# Power.net
KiCad netlist of a schematic drawn in Altium Designer
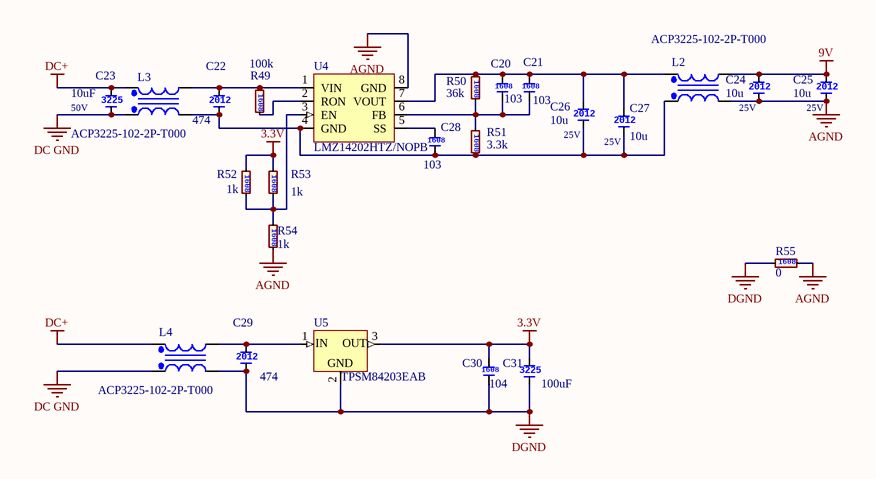
[diagram p0: Power.SchDoc]

(export (version "E")
  (design (tool "Eeschema 10.0.6"))
  (components
    (comp (ref "C20")
      (value "GCD188R71H103KA01D")
      (footprint "C1608")
      (description "セラコン1608サイズ")
      (fields (field (name "TAG") "103") (field (name "VOLTAGE") "50V"))
      (libsource (lib "Audio") (part "C1608"))
    )
    (comp (ref "C21")
      (value "GCD188R71H103KA01D")
      (footprint "C1608")
      (description "セラコン1608サイズ")
      (fields (field (name "TAG") "103") (field (name "VOLTAGE") "50V"))
      (libsource (lib "Audio") (part "C1608"))
    )
    (comp (ref "C22")
      (value "GRM21BR71H474MA88")
      (footprint "C2012")
      (description "セラコン2012サイズ")
      (fields (field (name "TAG") "474") (field (name "VOLTAGE") "50V"))
      (libsource (lib "Audio") (part "C2012"))
    )
    (comp (ref "C23")
      (value "UMK325C7106MM-T")
      (footprint "C3225")
      (description "セラコン3225サイズ")
      (fields (field (name "TAG") "10uF") (field (name "VOLTAGE") "50V"))
      (libsource (lib "Audio") (part "C3225"))
    )
    (comp (ref "C24")
      (value "TMK212BBJ106MG-T")
      (footprint "C2012")
      (description "セラコン2012サイズ")
      (fields (field (name "TAG") "10u") (field (name "VOLTAGE") "25V"))
      (libsource (lib "Audio") (part "C2012"))
    )
    (comp (ref "C25")
      (value "TMK212BBJ106MG-T")
      (footprint "C2012")
      (description "セラコン2012サイズ")
      (fields (field (name "TAG") "10u") (field (name "VOLTAGE") "25V"))
      (libsource (lib "Audio") (part "C2012"))
    )
    (comp (ref "C26")
      (value "TMK212BBJ106MG-T")
      (footprint "C2012")
      (description "セラコン2012サイズ")
      (fields (field (name "TAG") "10u") (field (name "VOLTAGE") "25V"))
      (libsource (lib "Audio") (part "C2012"))
    )
    (comp (ref "C27")
      (value "TMK212BBJ106MG-T")
      (footprint "C2012")
      (description "セラコン2012サイズ")
      (fields (field (name "TAG") "10u") (field (name "VOLTAGE") "25V"))
      (libsource (lib "Audio") (part "C2012"))
    )
    (comp (ref "C28")
      (value "GCD188R71H103KA01D")
      (footprint "C1608")
      (description "セラコン1608サイズ")
      (fields (field (name "TAG") "103") (field (name "VOLTAGE") "50V"))
      (libsource (lib "Audio") (part "C1608"))
    )
    (comp (ref "C29")
      (value "GRM21BR71H474MA88")
      (footprint "C2012")
      (description "セラコン2012サイズ")
      (fields (field (name "TAG") "474") (field (name "VOLTAGE") "50V"))
      (libsource (lib "Audio") (part "C2012"))
    )
    (comp (ref "C30")
      (value "CGA3E2X7R1H104K080AA")
      (footprint "C1608")
      (description "セラコン1608サイズ")
      (fields (field (name "TAG") "104") (field (name "VOLTAGE") "50V"))
      (libsource (lib "Audio") (part "C1608"))
    )
    (comp (ref "C31")
      (value "EMK325ABJ107MM-T")
      (footprint "C3225")
      (description "セラコン3225サイズ")
      (fields (field (name "TAG") "100uF") (field (name "VOLTAGE") "50V"))
      (libsource (lib "Audio") (part "C3225"))
    )
    (comp (ref "L2")
      (value "ACP3225-102-2P-T000")
      (footprint "ACM3225")
      (description "コモンモード,1A,4ピン")
      (libsource (lib "Audio") (part "ACM3225"))
    )
    (comp (ref "L3")
      (value "ACP3225-102-2P-T000")
      (footprint "ACM3225")
      (description "コモンモード,1A,4ピン")
      (libsource (lib "Audio Prj") (part "ACM3225"))
    )
    (comp (ref "L4")
      (value "ACP3225-102-2P-T000")
      (footprint "ACM3225")
      (description "コモンモード,1A,4ピン")
      (libsource (lib "Audio") (part "ACM3225"))
    )
    (comp (ref "R49")
      (value "ERJ-PA3F1003V")
      (footprint "R1608")
      (description "厚膜チップ抵抗1608サイズ")
      (fields (field (name "TAG") "100k"))
      (libsource (lib "Schlib1") (part "TF1608"))
    )
    (comp (ref "R50")
      (value "ERJ-PA3F3602V")
      (footprint "R1608")
      (description "厚膜チップ抵抗1608サイズ")
      (fields (field (name "TAG") "36k"))
      (libsource (lib "Schlib1") (part "TF1608"))
    )
    (comp (ref "R51")
      (value "ERJ-PA3F3301V")
      (footprint "R1608")
      (description "厚膜チップ抵抗1608サイズ")
      (fields (field (name "TAG") "3.3k"))
      (libsource (lib "Schlib1") (part "TF1608"))
    )
    (comp (ref "R52")
      (value "ERJ-PA3F1000V")
      (footprint "R1608")
      (description "厚膜チップ抵抗1608サイズ")
      (fields (field (name "TAG") "1k"))
      (libsource (lib "Schlib1") (part "TF1608"))
    )
    (comp (ref "R53")
      (value "ERJ-PA3F1000V")
      (footprint "R1608")
      (description "厚膜チップ抵抗1608サイズ")
      (fields (field (name "TAG") "1k"))
      (libsource (lib "Schlib1") (part "TF1608"))
    )
    (comp (ref "R54")
      (value "ERJ-PA3F1000V")
      (footprint "R1608")
      (description "厚膜チップ抵抗1608サイズ")
      (fields (field (name "TAG") "1k"))
      (libsource (lib "Schlib1") (part "TF1608"))
    )
    (comp (ref "R55")
      (value "ERJ-S030R00V")
      (footprint "R1608")
      (description "厚膜チップ抵抗1608サイズ")
      (fields (field (name "TAG") "0"))
      (libsource (lib "") (part "TF1608_1"))
    )
    (comp (ref "U4")
      (value "LMZ14202HTZ/NOPB")
      (footprint "TO-PMOD-7")
      (description "DC DC CONVERTER 5-30V")
      (libsource (lib "Audio") (part "LMZ14202HTZ/NOPB"))
    )
    (comp (ref "U5")
      (value "TPSM84203EAB")
      (footprint "TO220-3")
      (description "DC DC CONVERTER 3.3V")
      (libsource (lib "Audio Prj") (part "TPSM84203EAB"))
    )
  )
  (nets
    (net (code "1") (name "3.3V") (class "Default")
      (node (ref "C30") (pin "2") (pinfunction "2_2") (pintype "passive"))
      (node (ref "C31") (pin "2") (pinfunction "2_2") (pintype "passive"))
      (node (ref "R52") (pin "1") (pinfunction "1_1") (pintype "passive"))
      (node (ref "R53") (pin "1") (pinfunction "1_1") (pintype "passive"))
      (node (ref "U5") (pin "3") (pinfunction "OUT_3") (pintype "output"))
    )
    (net (code "2") (name "9V") (class "Default")
      (node (ref "C24") (pin "2") (pinfunction "2_2") (pintype "passive"))
      (node (ref "C25") (pin "2") (pinfunction "2_2") (pintype "passive"))
      (node (ref "L2") (pin "4") (pinfunction "Pri+_4") (pintype "passive"))
    )
    (net (code "3") (name "AGND") (class "Default")
      (node (ref "C24") (pin "1") (pinfunction "1_1") (pintype "passive"))
      (node (ref "C25") (pin "1") (pinfunction "1_1") (pintype "passive"))
      (node (ref "L2") (pin "3") (pinfunction "Pri-_3") (pintype "passive"))
      (node (ref "R54") (pin "2") (pinfunction "2_2") (pintype "passive"))
      (node (ref "R55") (pin "2") (pinfunction "2_2") (pintype "passive"))
      (node (ref "U4") (pin "8") (pinfunction "GND_8") (pintype "power_in"))
    )
    (net (code "4") (name "DC GND") (class "Default")
      (node (ref "C23") (pin "1") (pinfunction "1_1") (pintype "passive"))
      (node (ref "L3") (pin "2") (pinfunction "Sec-_2") (pintype "passive"))
      (node (ref "L4") (pin "2") (pinfunction "Sec-_2") (pintype "passive"))
    )
    (net (code "5") (name "DC+") (class "Default")
      (node (ref "C23") (pin "2") (pinfunction "2_2") (pintype "passive"))
      (node (ref "L3") (pin "1") (pinfunction "Sec+_1") (pintype "passive"))
      (node (ref "L4") (pin "1") (pinfunction "Sec+_1") (pintype "passive"))
    )
    (net (code "6") (name "DGND") (class "Default")
      (node (ref "C29") (pin "1") (pinfunction "1_1") (pintype "passive"))
      (node (ref "C30") (pin "1") (pinfunction "1_1") (pintype "passive"))
      (node (ref "C31") (pin "1") (pinfunction "1_1") (pintype "passive"))
      (node (ref "L4") (pin "3") (pinfunction "Pri-_3") (pintype "passive"))
      (node (ref "R55") (pin "1") (pinfunction "1_1") (pintype "passive"))
      (node (ref "U5") (pin "2") (pinfunction "GND_2") (pintype "power_in"))
    )
    (net (code "7") (name "Net-(L2-Sec+)") (class "Default")
      (node (ref "C20") (pin "2") (pinfunction "2_2") (pintype "passive"))
      (node (ref "C21") (pin "2") (pinfunction "2_2") (pintype "passive"))
      (node (ref "C26") (pin "2") (pinfunction "2_2") (pintype "passive"))
      (node (ref "C27") (pin "2") (pinfunction "2_2") (pintype "passive"))
      (node (ref "L2") (pin "1") (pinfunction "Sec+_1") (pintype "passive"))
      (node (ref "R50") (pin "1") (pinfunction "1_1") (pintype "passive"))
      (node (ref "U4") (pin "7") (pinfunction "VOUT_7") (pintype "power_in"))
    )
    (net (code "8") (name "Net-(L2-Sec-)") (class "Default")
      (node (ref "C22") (pin "1") (pinfunction "1_1") (pintype "passive"))
      (node (ref "C26") (pin "1") (pinfunction "1_1") (pintype "passive"))
      (node (ref "C27") (pin "1") (pinfunction "1_1") (pintype "passive"))
      (node (ref "C28") (pin "1") (pinfunction "1_1") (pintype "passive"))
      (node (ref "L2") (pin "2") (pinfunction "Sec-_2") (pintype "passive"))
      (node (ref "L3") (pin "3") (pinfunction "Pri-_3") (pintype "passive"))
      (node (ref "R51") (pin "2") (pinfunction "2_2") (pintype "passive"))
      (node (ref "U4") (pin "4") (pinfunction "GND_4") (pintype "power_in"))
    )
    (net (code "9") (name "Net-(L3-Pri+)") (class "Default")
      (node (ref "C22") (pin "2") (pinfunction "2_2") (pintype "passive"))
      (node (ref "L3") (pin "4") (pinfunction "Pri+_4") (pintype "passive"))
      (node (ref "R49") (pin "1") (pinfunction "1_1") (pintype "passive"))
      (node (ref "U4") (pin "1") (pinfunction "VIN_1") (pintype "power_in"))
    )
    (net (code "10") (name "Net-(L4-Pri+)") (class "Default")
      (node (ref "C29") (pin "2") (pinfunction "2_2") (pintype "passive"))
      (node (ref "L4") (pin "4") (pinfunction "Pri+_4") (pintype "passive"))
      (node (ref "U5") (pin "1") (pinfunction "IN_1") (pintype "input"))
    )
    (net (code "11") (name "Net-(U4-EN)") (class "Default")
      (node (ref "R52") (pin "2") (pinfunction "2_2") (pintype "passive"))
      (node (ref "R53") (pin "2") (pinfunction "2_2") (pintype "passive"))
      (node (ref "R54") (pin "1") (pinfunction "1_1") (pintype "passive"))
      (node (ref "U4") (pin "3") (pinfunction "EN_3") (pintype "input"))
    )
    (net (code "12") (name "Net-(U4-FB)") (class "Default")
      (node (ref "C20") (pin "1") (pinfunction "1_1") (pintype "passive"))
      (node (ref "C21") (pin "1") (pinfunction "1_1") (pintype "passive"))
      (node (ref "R50") (pin "2") (pinfunction "2_2") (pintype "passive"))
      (node (ref "R51") (pin "1") (pinfunction "1_1") (pintype "passive"))
      (node (ref "U4") (pin "6") (pinfunction "FB_6") (pintype "passive"))
    )
    (net (code "13") (name "Net-(U4-RON)") (class "Default")
      (node (ref "R49") (pin "2") (pinfunction "2_2") (pintype "passive"))
      (node (ref "U4") (pin "2") (pinfunction "RON_2") (pintype "passive"))
    )
    (net (code "14") (name "Net-(U4-SS)") (class "Default")
      (node (ref "C28") (pin "2") (pinfunction "2_2") (pintype "passive"))
      (node (ref "U4") (pin "5") (pinfunction "SS_5") (pintype "passive"))
    )
  )
)
